# GW-RS485-V40-009.net
KiCad netlist of a schematic drawn in EAGLE
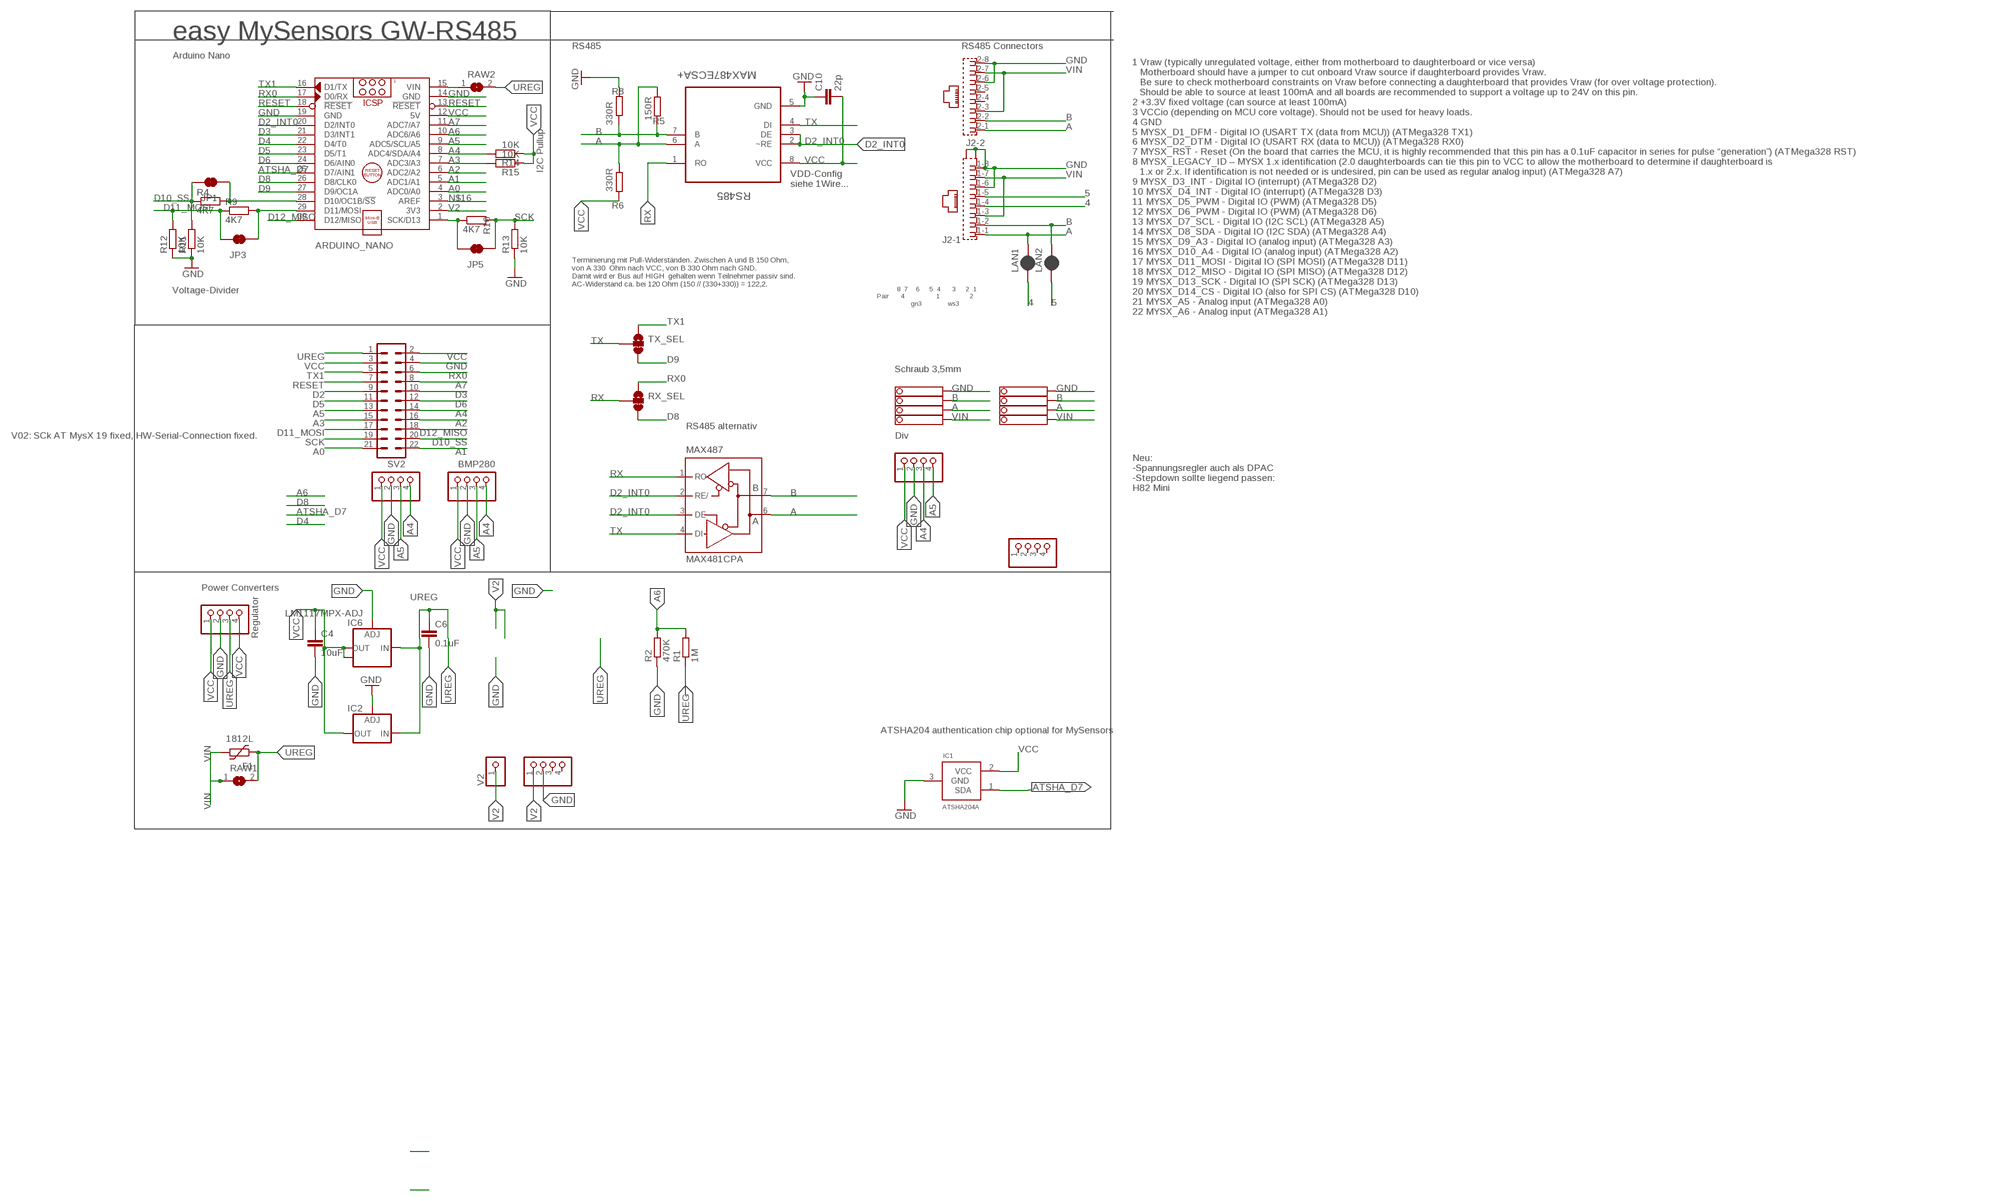
[diagram p0: schematic, sheet 1]

(export (version "E")
  (design (tool "Eeschema 10.0.6"))
  (components
    (comp (ref "ARDUINO_NANO")
      (value "ARDUINO_NANO_OHNE-BOHR")
      (footprint "eagle-import:ARDUINO_NANO")
      (libsource (lib "eagle-import") (part "ARDUINO_NANO_OHNE-BOHR"))
    )
    (comp (ref "BH1750")
      (value "PINHD-1X04_2.54-S")
      (footprint "eagle-import:1X04-S")
      (libsource (lib "eagle-import") (part "PINHD-1X04_2.54-S"))
    )
    (comp (ref "C4")
      (value "10uF")
      (footprint "eagle-import:C1210")
      (libsource (lib "eagle-import") (part "C-EUC1210"))
    )
    (comp (ref "C6")
      (value "0.1uF")
      (footprint "eagle-import:C1206")
      (libsource (lib "eagle-import") (part "C-EUC1206"))
    )
    (comp (ref "C10")
      (value "22p")
      (footprint "eagle-import:C0805")
      (libsource (lib "eagle-import") (part "C-EUC0805"))
    )
    (comp (ref "F1")
      (value "1812L")
      (footprint "eagle-import:1812L")
      (libsource (lib "eagle-import") (part "1812L"))
    )
    (comp (ref "I2C-1")
      (value "PINHD-1X04_2.54-S")
      (footprint "eagle-import:1X04-S")
      (libsource (lib "eagle-import") (part "PINHD-1X04_2.54-S"))
    )
    (comp (ref "I2C-2")
      (value "PINHD-1X04_2.54-S")
      (footprint "eagle-import:1X04-S")
      (libsource (lib "eagle-import") (part "PINHD-1X04_2.54-S"))
    )
    (comp (ref "IC1")
      (value "ATSHA204A")
      (footprint "eagle-import:SOT23")
      (libsource (lib "eagle-import") (part "ATSHA204A"))
    )
    (comp (ref "IC2")
      (value "LD117ADT50TR")
      (footprint "eagle-import:DPACK")
      (libsource (lib "eagle-import") (part "LD117A?DT50TR"))
    )
    (comp (ref "IC6")
      (value "LM1117MPX-ADJ")
      (footprint "eagle-import:SOT223")
      (libsource (lib "eagle-import") (part "LM1117MPX-ADJ"))
    )
    (comp (ref "J2")
      (value "RJ45_2X_NARROW_SHILDPINS_NOCASE")
      (footprint "eagle-import:RJ45_2X_NARROW_SHILDPINS_NOCASE")
      (libsource (lib "eagle-import") (part "RJ45_2X_NARROW_SHILDPINS_NOCASE"))
    )
    (comp (ref "JP1")
      (value "JUMPER-SMT_2_NC_TRACE_SILK")
      (footprint "eagle-import:SMT-JUMPER_2_NC_TRACE_SILK")
      (libsource (lib "eagle-import") (part "JUMPER-SMT_2_NC_TRACE_SILK"))
    )
    (comp (ref "JP2")
      (value "PINHD-1X04_2.54-S")
      (footprint "eagle-import:1X04-S")
      (libsource (lib "eagle-import") (part "PINHD-1X04_2.54-S"))
    )
    (comp (ref "JP3")
      (value "JUMPER-SMT_2_NC_TRACE_SILK")
      (footprint "eagle-import:SMT-JUMPER_2_NC_TRACE_SILK")
      (libsource (lib "eagle-import") (part "JUMPER-SMT_2_NC_TRACE_SILK"))
    )
    (comp (ref "JP5")
      (value "JUMPER-SMT_2_NC_TRACE_SILK")
      (footprint "eagle-import:SMT-JUMPER_2_NC_TRACE_SILK")
      (libsource (lib "eagle-import") (part "JUMPER-SMT_2_NC_TRACE_SILK"))
    )
    (comp (ref "LAN1")
      (value "JUMPER-SMT_2_NC_PASTE_SILK")
      (footprint "eagle-import:SMT-JUMPER_2_NC_PASTE_SILK")
      (libsource (lib "eagle-import") (part "JUMPER-SMT_2_NC_PASTE_SILK"))
    )
    (comp (ref "LAN2")
      (value "JUMPER-SMT_2_NC_PASTE_SILK")
      (footprint "eagle-import:SMT-JUMPER_2_NC_PASTE_SILK")
      (libsource (lib "eagle-import") (part "JUMPER-SMT_2_NC_PASTE_SILK"))
    )
    (comp (ref "MAX487")
      (value "MAX481CPA")
      (footprint "eagle-import:DIL08")
      (libsource (lib "eagle-import") (part "MAX481CPA"))
    )
    (comp (ref "R1")
      (value "1M")
      (footprint "eagle-import:R0805")
      (libsource (lib "eagle-import") (part "R-EU_R0805"))
    )
    (comp (ref "R2")
      (value "470K")
      (footprint "eagle-import:R0805")
      (libsource (lib "eagle-import") (part "R-EU_R0805"))
    )
    (comp (ref "R4")
      (value "4K7")
      (footprint "eagle-import:M0805")
      (libsource (lib "eagle-import") (part "R-EU_M0805"))
    )
    (comp (ref "R5")
      (value "150R")
      (footprint "eagle-import:R0805")
      (libsource (lib "eagle-import") (part "R-EU_R0805"))
    )
    (comp (ref "R6")
      (value "330R")
      (footprint "eagle-import:R0805")
      (libsource (lib "eagle-import") (part "R-EU_R0805"))
    )
    (comp (ref "R8")
      (value "330R")
      (footprint "eagle-import:R0805")
      (libsource (lib "eagle-import") (part "R-EU_R0805"))
    )
    (comp (ref "R9")
      (value "4K7")
      (footprint "eagle-import:M0805")
      (libsource (lib "eagle-import") (part "R-EU_M0805"))
    )
    (comp (ref "R10")
      (value "4K7")
      (footprint "eagle-import:M0805")
      (libsource (lib "eagle-import") (part "R-EU_M0805"))
    )
    (comp (ref "R11")
      (value "10K")
      (footprint "eagle-import:M0805")
      (libsource (lib "eagle-import") (part "R-EU_M0805"))
    )
    (comp (ref "R12")
      (value "10K")
      (footprint "eagle-import:M0805")
      (libsource (lib "eagle-import") (part "R-EU_M0805"))
    )
    (comp (ref "R13")
      (value "10K")
      (footprint "eagle-import:M0805")
      (libsource (lib "eagle-import") (part "R-EU_M0805"))
    )
    (comp (ref "R14")
      (value "10K")
      (footprint "eagle-import:R0805")
      (libsource (lib "eagle-import") (part "R-EU_R0805"))
    )
    (comp (ref "R15")
      (value "10K")
      (footprint "eagle-import:R0805")
      (libsource (lib "eagle-import") (part "R-EU_R0805"))
    )
    (comp (ref "RAW1")
      (value "SJ")
      (footprint "eagle-import:SJ")
      (libsource (lib "eagle-import") (part "SJ"))
    )
    (comp (ref "RAW2")
      (value "SJ")
      (footprint "eagle-import:SJ")
      (libsource (lib "eagle-import") (part "SJ"))
    )
    (comp (ref "RS485")
      (value "MAX487ECSA+")
      (footprint "eagle-import:SOIC127P600X175-8N")
      (libsource (lib "eagle-import") (part "MAX487ECSA+"))
    )
    (comp (ref "RX_SEL")
      (value "JUMPER-SMT_3_1-NC_TRACE_SILK")
      (footprint "eagle-import:SMT-JUMPER_3_1-NC_TRACE_SILK")
      (libsource (lib "eagle-import") (part "JUMPER-SMT_3_1-NC_TRACE_SILK"))
    )
    (comp (ref "STEPDWN")
      (value "PINHD-1X04_2.54-S")
      (footprint "eagle-import:1X04-S")
      (libsource (lib "eagle-import") (part "PINHD-1X04_2.54-S"))
    )
    (comp (ref "SV2")
      (value "MA11-2")
      (footprint "eagle-import:MA11-2")
      (libsource (lib "eagle-import") (part "MA11-2"))
    )
    (comp (ref "TX_SEL")
      (value "JUMPER-SMT_3_1-NC_TRACE_SILK")
      (footprint "eagle-import:SMT-JUMPER_3_1-NC_TRACE_SILK")
      (libsource (lib "eagle-import") (part "JUMPER-SMT_3_1-NC_TRACE_SILK"))
    )
    (comp (ref "V2")
      (value "PINHD-1X1")
      (footprint "eagle-import:1X01")
      (libsource (lib "eagle-import") (part "PINHD-1X1"))
    )
    (comp (ref "V2-")
      (value "PINHD-1X04_2.54-S")
      (footprint "eagle-import:1X04-S")
      (libsource (lib "eagle-import") (part "PINHD-1X04_2.54-S"))
    )
    (comp (ref "X1")
      (value "1751264")
      (footprint "eagle-import:1751264")
      (libsource (lib "eagle-import") (part "1751264"))
    )
    (comp (ref "X4")
      (value "1751264")
      (footprint "eagle-import:1751264")
      (libsource (lib "eagle-import") (part "1751264"))
    )
  )
  (nets
    (net (code "1") (name "/4") (class "Default")
      (node (ref "J2") (pin "1-4") (pinfunction "4_1-4") (pintype "passive"))
      (node (ref "LAN1") (pin "1") (pinfunction "1_1") (pintype "passive"))
    )
    (net (code "2") (name "/5") (class "Default")
      (node (ref "J2") (pin "1-5") (pinfunction "5_1-5") (pintype "passive"))
      (node (ref "LAN2") (pin "1") (pinfunction "1_1") (pintype "passive"))
    )
    (net (code "3") (name "/A") (class "Default")
      (node (ref "J2") (pin "1-1") (pinfunction "1_1-1") (pintype "passive"))
      (node (ref "J2") (pin "2-1") (pinfunction "1_2-1") (pintype "passive"))
      (node (ref "LAN1") (pin "2") (pinfunction "2_2") (pintype "passive"))
      (node (ref "MAX487") (pin "6") (pinfunction "A_6") (pintype "passive"))
      (node (ref "R5") (pin "1") (pinfunction "1_1") (pintype "passive"))
      (node (ref "R6") (pin "2") (pinfunction "2_2") (pintype "passive"))
      (node (ref "RS485") (pin "6") (pinfunction "A_6") (pintype "bidirectional"))
      (node (ref "X1") (pin "2") (pinfunction "K_2") (pintype "passive"))
      (node (ref "X4") (pin "2") (pinfunction "K_2") (pintype "passive"))
    )
    (net (code "4") (name "/A0") (class "Default")
      (node (ref "ARDUINO_NANO") (pin "4") (pinfunction "ADC0/A0_4") (pintype "bidirectional"))
      (node (ref "SV2") (pin "21") (pinfunction "21_21") (pintype "passive"))
    )
    (net (code "5") (name "/A1") (class "Default")
      (node (ref "ARDUINO_NANO") (pin "5") (pinfunction "ADC1/A1_5") (pintype "bidirectional"))
      (node (ref "SV2") (pin "22") (pinfunction "22_22") (pintype "passive"))
    )
    (net (code "6") (name "/A2") (class "Default")
      (node (ref "ARDUINO_NANO") (pin "6") (pinfunction "ADC2/A2_6") (pintype "bidirectional"))
      (node (ref "SV2") (pin "16") (pinfunction "16_16") (pintype "passive"))
    )
    (net (code "7") (name "/A3") (class "Default")
      (node (ref "ARDUINO_NANO") (pin "7") (pinfunction "ADC3/A3_7") (pintype "bidirectional"))
      (node (ref "R15") (pin "2") (pinfunction "2_2") (pintype "passive"))
      (node (ref "SV2") (pin "15") (pinfunction "15_15") (pintype "passive"))
    )
    (net (code "8") (name "/A7") (class "Default")
      (node (ref "ARDUINO_NANO") (pin "11") (pinfunction "ADC7/A7_11") (pintype "bidirectional"))
      (node (ref "SV2") (pin "8") (pinfunction "8_8") (pintype "passive"))
    )
    (net (code "9") (name "/ATSHA_D7") (class "Default")
      (node (ref "ARDUINO_NANO") (pin "25") (pinfunction "D7/AIN1_25") (pintype "bidirectional"))
      (node (ref "IC1") (pin "1") (pinfunction "SDA_1") (pintype "bidirectional"))
    )
    (net (code "10") (name "/B") (class "Default")
      (node (ref "J2") (pin "1-2") (pinfunction "2_1-2") (pintype "passive"))
      (node (ref "J2") (pin "2-2") (pinfunction "2_2-2") (pintype "passive"))
      (node (ref "LAN2") (pin "2") (pinfunction "2_2") (pintype "passive"))
      (node (ref "MAX487") (pin "7") (pinfunction "B_7") (pintype "passive"))
      (node (ref "R5") (pin "2") (pinfunction "2_2") (pintype "passive"))
      (node (ref "R8") (pin "1") (pinfunction "1_1") (pintype "passive"))
      (node (ref "RS485") (pin "7") (pinfunction "B_7") (pintype "bidirectional"))
      (node (ref "X1") (pin "3") (pinfunction "K_3") (pintype "passive"))
      (node (ref "X4") (pin "3") (pinfunction "K_3") (pintype "passive"))
    )
    (net (code "11") (name "/D2") (class "Default")
      (node (ref "SV2") (pin "9") (pinfunction "9_9") (pintype "passive"))
    )
    (net (code "12") (name "/D3") (class "Default")
      (node (ref "ARDUINO_NANO") (pin "21") (pinfunction "D3/INT1_21") (pintype "bidirectional"))
      (node (ref "SV2") (pin "10") (pinfunction "10_10") (pintype "passive"))
    )
    (net (code "13") (name "/D4") (class "Default")
      (node (ref "ARDUINO_NANO") (pin "22") (pinfunction "D4/T0_22") (pintype "bidirectional"))
    )
    (net (code "14") (name "/D5") (class "Default")
      (node (ref "ARDUINO_NANO") (pin "23") (pinfunction "D5/T1_23") (pintype "bidirectional"))
      (node (ref "SV2") (pin "11") (pinfunction "11_11") (pintype "passive"))
    )
    (net (code "15") (name "/D6") (class "Default")
      (node (ref "ARDUINO_NANO") (pin "24") (pinfunction "D6/AIN0_24") (pintype "bidirectional"))
      (node (ref "SV2") (pin "12") (pinfunction "12_12") (pintype "passive"))
    )
    (net (code "16") (name "/D8") (class "Default")
      (node (ref "ARDUINO_NANO") (pin "26") (pinfunction "D8/CLK0_26") (pintype "bidirectional"))
      (node (ref "RX_SEL") (pin "3") (pinfunction "3_3") (pintype "passive"))
    )
    (net (code "17") (name "/D9") (class "Default")
      (node (ref "ARDUINO_NANO") (pin "27") (pinfunction "D9/OC1A_27") (pintype "bidirectional"))
      (node (ref "TX_SEL") (pin "3") (pinfunction "3_3") (pintype "passive"))
    )
    (net (code "18") (name "/D10_SS") (class "Default")
      (node (ref "JP1") (pin "1") (pinfunction "1_1") (pintype "passive"))
      (node (ref "R11") (pin "2") (pinfunction "2_2") (pintype "passive"))
      (node (ref "R4") (pin "1") (pinfunction "1_1") (pintype "passive"))
      (node (ref "SV2") (pin "20") (pinfunction "20_20") (pintype "passive"))
    )
    (net (code "19") (name "/D11_MOSI") (class "Default")
      (node (ref "JP3") (pin "1") (pinfunction "1_1") (pintype "passive"))
      (node (ref "R12") (pin "2") (pinfunction "2_2") (pintype "passive"))
      (node (ref "R9") (pin "1") (pinfunction "1_1") (pintype "passive"))
      (node (ref "SV2") (pin "17") (pinfunction "17_17") (pintype "passive"))
    )
    (net (code "20") (name "/D12_MISO") (class "Default")
      (node (ref "ARDUINO_NANO") (pin "30") (pinfunction "D12/MISO_30") (pintype "bidirectional"))
      (node (ref "SV2") (pin "18") (pinfunction "18_18") (pintype "passive"))
    )
    (net (code "21") (name "/N$16") (class "Default")
      (node (ref "ARDUINO_NANO") (pin "3") (pinfunction "AREF_3") (pintype "input"))
    )
    (net (code "22") (name "/RESET") (class "Default")
      (node (ref "ARDUINO_NANO") (pin "13") (pinfunction "~{RESET}_13") (pintype "input"))
      (node (ref "ARDUINO_NANO") (pin "18") (pinfunction "~{RESET}_18") (pintype "input"))
      (node (ref "SV2") (pin "7") (pinfunction "7_7") (pintype "passive"))
    )
    (net (code "23") (name "/RX0") (class "Default")
      (node (ref "ARDUINO_NANO") (pin "17") (pinfunction "D0/RX_17") (pintype "bidirectional"))
      (node (ref "RX_SEL") (pin "1") (pinfunction "1_1") (pintype "passive"))
      (node (ref "SV2") (pin "6") (pinfunction "6_6") (pintype "passive"))
    )
    (net (code "24") (name "/SCK") (class "Default")
      (node (ref "JP5") (pin "2") (pinfunction "2_2") (pintype "passive"))
      (node (ref "R10") (pin "2") (pinfunction "2_2") (pintype "passive"))
      (node (ref "R13") (pin "2") (pinfunction "2_2") (pintype "passive"))
      (node (ref "SV2") (pin "19") (pinfunction "19_19") (pintype "passive"))
    )
    (net (code "25") (name "/TX") (class "Default")
      (node (ref "MAX487") (pin "4") (pinfunction "DI_4") (pintype "input"))
      (node (ref "RS485") (pin "4") (pinfunction "DI_4") (pintype "input"))
      (node (ref "TX_SEL") (pin "2") (pinfunction "2_2") (pintype "passive"))
    )
    (net (code "26") (name "/TX1") (class "Default")
      (node (ref "ARDUINO_NANO") (pin "16") (pinfunction "D1/TX_16") (pintype "bidirectional"))
      (node (ref "SV2") (pin "5") (pinfunction "5_5") (pintype "passive"))
      (node (ref "TX_SEL") (pin "1") (pinfunction "1_1") (pintype "passive"))
    )
    (net (code "27") (name "/VIN") (class "Default")
      (node (ref "F1") (pin "P$2") (pinfunction "2_P$2") (pintype "passive"))
      (node (ref "J2") (pin "1-3") (pinfunction "3_1-3") (pintype "passive"))
      (node (ref "J2") (pin "1-7") (pinfunction "7_1-7") (pintype "passive"))
      (node (ref "J2") (pin "2-3") (pinfunction "3_2-3") (pintype "passive"))
      (node (ref "J2") (pin "2-7") (pinfunction "7_2-7") (pintype "passive"))
      (node (ref "RAW1") (pin "1") (pinfunction "1_1") (pintype "passive"))
      (node (ref "X1") (pin "1") (pinfunction "K_1") (pintype "passive"))
      (node (ref "X4") (pin "1") (pinfunction "K_1") (pintype "passive"))
    )
    (net (code "28") (name "A4") (class "Default")
      (node (ref "ARDUINO_NANO") (pin "8") (pinfunction "ADC4/SDA/A4_8") (pintype "bidirectional"))
      (node (ref "BH1750") (pin "4") (pinfunction "4_4") (pintype "passive"))
      (node (ref "I2C-1") (pin "4") (pinfunction "4_4") (pintype "passive"))
      (node (ref "I2C-2") (pin "3") (pinfunction "3_3") (pintype "passive"))
      (node (ref "R14") (pin "2") (pinfunction "2_2") (pintype "passive"))
      (node (ref "SV2") (pin "14") (pinfunction "14_14") (pintype "passive"))
    )
    (net (code "29") (name "A5") (class "Default")
      (node (ref "ARDUINO_NANO") (pin "9") (pinfunction "ADC5/SCL/A5_9") (pintype "bidirectional"))
      (node (ref "BH1750") (pin "3") (pinfunction "3_3") (pintype "passive"))
      (node (ref "I2C-1") (pin "3") (pinfunction "3_3") (pintype "passive"))
      (node (ref "I2C-2") (pin "4") (pinfunction "4_4") (pintype "passive"))
      (node (ref "SV2") (pin "13") (pinfunction "13_13") (pintype "passive"))
    )
    (net (code "30") (name "A6") (class "Default")
      (node (ref "ARDUINO_NANO") (pin "10") (pinfunction "ADC6/A6_10") (pintype "bidirectional"))
      (node (ref "R1") (pin "2") (pinfunction "2_2") (pintype "passive"))
      (node (ref "R2") (pin "2") (pinfunction "2_2") (pintype "passive"))
    )
    (net (code "31") (name "D2_INT0") (class "Default")
      (node (ref "ARDUINO_NANO") (pin "20") (pinfunction "D2/INT0_20") (pintype "bidirectional"))
      (node (ref "MAX487") (pin "2") (pinfunction "RE/_2") (pintype "input"))
      (node (ref "MAX487") (pin "3") (pinfunction "DE_3") (pintype "input"))
      (node (ref "RS485") (pin "2") (pinfunction "~{RE}_2") (pintype "input"))
      (node (ref "RS485") (pin "3") (pinfunction "DE_3") (pintype "input"))
    )
    (net (code "32") (name "GND") (class "Default")
      (node (ref "ARDUINO_NANO") (pin "14") (pinfunction "GND_14") (pintype "power_in"))
      (node (ref "ARDUINO_NANO") (pin "19") (pinfunction "GND_19") (pintype "power_in"))
      (node (ref "BH1750") (pin "2") (pinfunction "2_2") (pintype "passive"))
      (node (ref "C10") (pin "1") (pinfunction "1_1") (pintype "passive"))
      (node (ref "C4") (pin "2") (pinfunction "2_2") (pintype "passive"))
      (node (ref "C6") (pin "2") (pinfunction "2_2") (pintype "passive"))
      (node (ref "I2C-1") (pin "2") (pinfunction "2_2") (pintype "passive"))
      (node (ref "I2C-2") (pin "2") (pinfunction "2_2") (pintype "passive"))
      (node (ref "IC1") (pin "3") (pinfunction "GND_3") (pintype "bidirectional"))
      (node (ref "IC2") (pin "1") (pinfunction "ADJ_1") (pintype "input"))
      (node (ref "IC6") (pin "1") (pinfunction "ADJ_1") (pintype "input"))
      (node (ref "J2") (pin "1-6") (pinfunction "6_1-6") (pintype "passive"))
      (node (ref "J2") (pin "1-8") (pinfunction "8_1-8") (pintype "passive"))
      (node (ref "J2") (pin "2-6") (pinfunction "6_2-6") (pintype "passive"))
      (node (ref "J2") (pin "2-8") (pinfunction "8_2-8") (pintype "passive"))
      (node (ref "J2") (pin "G1") (pinfunction "S1_G1") (pintype "passive"))
      (node (ref "J2") (pin "G3") (pinfunction "S2_G3") (pintype "passive"))
      (node (ref "R11") (pin "1") (pinfunction "1_1") (pintype "passive"))
      (node (ref "R12") (pin "1") (pinfunction "1_1") (pintype "passive"))
      (node (ref "R13") (pin "1") (pinfunction "1_1") (pintype "passive"))
      (node (ref "R2") (pin "1") (pinfunction "1_1") (pintype "passive"))
      (node (ref "R8") (pin "2") (pinfunction "2_2") (pintype "passive"))
      (node (ref "RS485") (pin "5") (pinfunction "GND_5") (pintype "passive"))
      (node (ref "STEPDWN") (pin "2") (pinfunction "2_2") (pintype "passive"))
      (node (ref "SV2") (pin "4") (pinfunction "4_4") (pintype "passive"))
      (node (ref "V2-") (pin "2") (pinfunction "2_2") (pintype "passive"))
      (node (ref "X1") (pin "4") (pinfunction "K_4") (pintype "passive"))
      (node (ref "X4") (pin "4") (pinfunction "K_4") (pintype "passive"))
    )
    (net (code "33") (name "Net-(ARDUINO_NANO-D10{slash}OC1B{slash}~{SS})") (class "Default")
      (node (ref "ARDUINO_NANO") (pin "28") (pinfunction "D10/OC1B/~{SS}_28") (pintype "bidirectional"))
      (node (ref "JP1") (pin "2") (pinfunction "2_2") (pintype "passive"))
      (node (ref "R4") (pin "2") (pinfunction "2_2") (pintype "passive"))
    )
    (net (code "34") (name "Net-(ARDUINO_NANO-D11{slash}MOSI)") (class "Default")
      (node (ref "ARDUINO_NANO") (pin "29") (pinfunction "D11/MOSI_29") (pintype "bidirectional"))
      (node (ref "JP3") (pin "2") (pinfunction "2_2") (pintype "passive"))
      (node (ref "R9") (pin "2") (pinfunction "2_2") (pintype "passive"))
    )
    (net (code "35") (name "Net-(ARDUINO_NANO-SCK{slash}D13)") (class "Default")
      (node (ref "ARDUINO_NANO") (pin "1") (pinfunction "SCK/D13_1") (pintype "bidirectional"))
      (node (ref "JP5") (pin "1") (pinfunction "1_1") (pintype "passive"))
      (node (ref "R10") (pin "1") (pinfunction "1_1") (pintype "passive"))
    )
    (net (code "36") (name "Net-(ARDUINO_NANO-VIN)") (class "Default")
      (node (ref "ARDUINO_NANO") (pin "15") (pinfunction "VIN_15") (pintype "power_in"))
      (node (ref "RAW2") (pin "1") (pinfunction "1_1") (pintype "passive"))
    )
    (net (code "37") (name "RX") (class "Default")
      (node (ref "MAX487") (pin "1") (pinfunction "RO_1") (pintype "output"))
      (node (ref "RS485") (pin "1") (pinfunction "RO_1") (pintype "output"))
      (node (ref "RX_SEL") (pin "2") (pinfunction "2_2") (pintype "passive"))
    )
    (net (code "38") (name "UREG") (class "Default")
      (node (ref "C6") (pin "1") (pinfunction "1_1") (pintype "passive"))
      (node (ref "F1") (pin "P$1") (pinfunction "1_P$1") (pintype "passive"))
      (node (ref "IC2") (pin "3") (pinfunction "IN_3") (pintype "input"))
      (node (ref "IC6") (pin "3") (pinfunction "IN_3") (pintype "input"))
      (node (ref "R1") (pin "1") (pinfunction "1_1") (pintype "passive"))
      (node (ref "RAW1") (pin "2") (pinfunction "2_2") (pintype "passive"))
      (node (ref "RAW2") (pin "2") (pinfunction "2_2") (pintype "passive"))
      (node (ref "STEPDWN") (pin "3") (pinfunction "3_3") (pintype "passive"))
      (node (ref "SV2") (pin "1") (pinfunction "1_1") (pintype "passive"))
    )
    (net (code "39") (name "V2") (class "Default")
      (node (ref "ARDUINO_NANO") (pin "2") (pinfunction "3V3_2") (pintype "output"))
      (node (ref "V2") (pin "1") (pinfunction "1_1") (pintype "passive"))
      (node (ref "V2-") (pin "1") (pinfunction "1_1") (pintype "passive"))
    )
    (net (code "40") (name "VCC") (class "Default")
      (node (ref "ARDUINO_NANO") (pin "12") (pinfunction "5V_12") (pintype "power_in"))
      (node (ref "BH1750") (pin "1") (pinfunction "1_1") (pintype "passive"))
      (node (ref "C10") (pin "2") (pinfunction "2_2") (pintype "passive"))
      (node (ref "C4") (pin "1") (pinfunction "1_1") (pintype "passive"))
      (node (ref "I2C-1") (pin "1") (pinfunction "1_1") (pintype "passive"))
      (node (ref "I2C-2") (pin "1") (pinfunction "1_1") (pintype "passive"))
      (node (ref "IC1") (pin "2") (pinfunction "VCC_2") (pintype "bidirectional"))
      (node (ref "IC2") (pin "4") (pinfunction "OUT_4") (pintype "passive"))
      (node (ref "IC6") (pin "2") (pinfunction "OUT_2") (pintype "passive"))
      (node (ref "IC6") (pin "TAB") (pinfunction "OUT1_TAB") (pintype "passive"))
      (node (ref "R14") (pin "1") (pinfunction "1_1") (pintype "passive"))
      (node (ref "R15") (pin "1") (pinfunction "1_1") (pintype "passive"))
      (node (ref "R6") (pin "1") (pinfunction "1_1") (pintype "passive"))
      (node (ref "RS485") (pin "8") (pinfunction "VCC_8") (pintype "power_in"))
      (node (ref "STEPDWN") (pin "1") (pinfunction "1_1") (pintype "passive"))
      (node (ref "STEPDWN") (pin "4") (pinfunction "4_4") (pintype "passive"))
      (node (ref "SV2") (pin "2") (pinfunction "2_2") (pintype "passive"))
      (node (ref "SV2") (pin "3") (pinfunction "3_3") (pintype "passive"))
    )
    (net (code "41") (name "unconnected-(J2B-4-Pad2-4)") (class "Default")
      (node (ref "J2") (pin "2-4") (pinfunction "4_2-4") (pintype "passive"))
    )
    (net (code "42") (name "unconnected-(J2B-5-Pad2-5)") (class "Default")
      (node (ref "J2") (pin "2-5") (pinfunction "5_2-5") (pintype "passive"))
    )
    (net (code "43") (name "unconnected-(JP2-Pad1)") (class "Default")
      (node (ref "JP2") (pin "1") (pinfunction "1_1") (pintype "passive"))
    )
    (net (code "44") (name "unconnected-(JP2-Pad2)") (class "Default")
      (node (ref "JP2") (pin "2") (pinfunction "2_2") (pintype "passive"))
    )
    (net (code "45") (name "unconnected-(JP2-Pad3)") (class "Default")
      (node (ref "JP2") (pin "3") (pinfunction "3_3") (pintype "passive"))
    )
    (net (code "46") (name "unconnected-(JP2-Pad4)") (class "Default")
      (node (ref "JP2") (pin "4") (pinfunction "4_4") (pintype "passive"))
    )
    (net (code "47") (name "unconnected-(V2--Pad3)") (class "Default")
      (node (ref "V2-") (pin "3") (pinfunction "3_3") (pintype "passive"))
    )
    (net (code "48") (name "unconnected-(V2--Pad4)") (class "Default")
      (node (ref "V2-") (pin "4") (pinfunction "4_4") (pintype "passive"))
    )
  )
)
